# MainBoard_V1p0_SD.net
KiCad netlist of a schematic drawn in Altium Designer
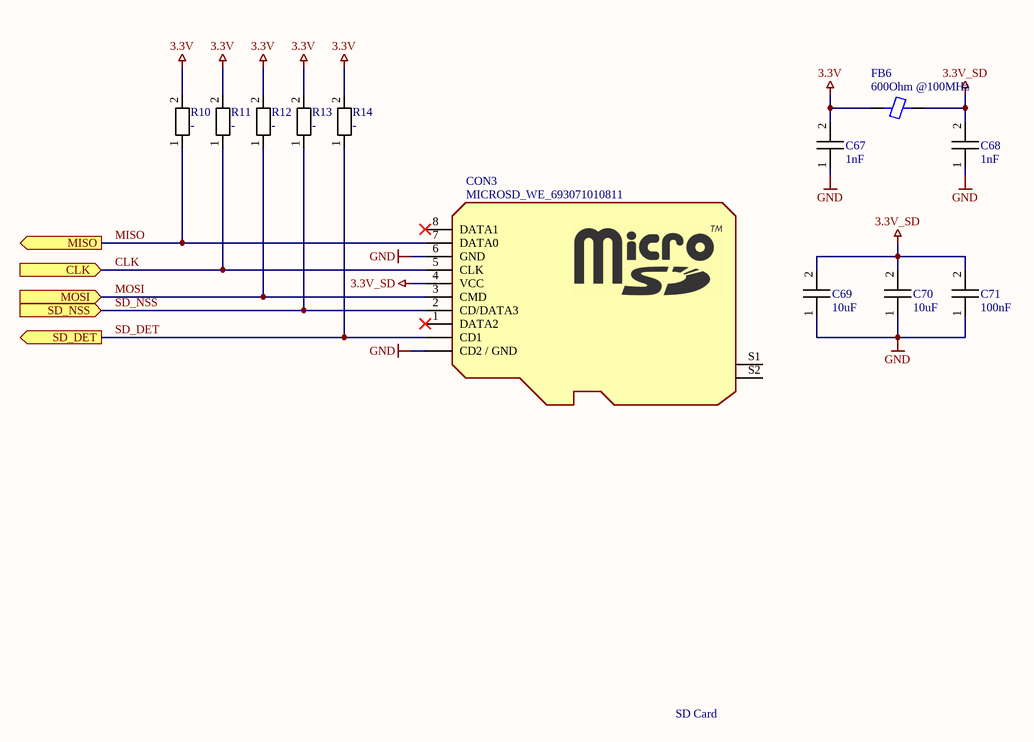
[diagram p0: MainBoard_V1p0_SD.SchDoc]

(export (version "E")
  (design (tool "Eeschema 10.0.6"))
  (components
    (comp (ref "C67") (value "1nF") (footprint "0805_C") (libsource (lib "Schlib1") (part "CAPACITOR")))
    (comp (ref "C68") (value "1nF") (footprint "0805_C") (libsource (lib "Schlib1") (part "CAPACITOR")))
    (comp (ref "C69") (value "10uF") (footprint "1210_C") (libsource (lib "Schlib1") (part "CAPACITOR")))
    (comp (ref "C70") (value "10uF") (footprint "1210_C") (libsource (lib "Schlib1") (part "CAPACITOR")))
    (comp (ref "C71") (value "100nF") (footprint "0805_C") (libsource (lib "Schlib1") (part "CAPACITOR")))
    (comp (ref "CON3")
      (value "MICROSD_WE_693071010811")
      (footprint "T_Wurth_693071010811")
      (libsource (lib "Schlib1") (part "MICROSD_WE_693071010811"))
    )
    (comp (ref "FB6")
      (value "600Ohm @100MHz")
      (footprint "0805_FB")
      (libsource (lib "Schlib1") (part "FERRITE_BEAD"))
    )
    (comp (ref "R10") (value "-") (footprint "0805") (libsource (lib "Schlib1") (part "RESISTOR")))
    (comp (ref "R11") (value "-") (footprint "0805") (libsource (lib "Schlib1") (part "RESISTOR")))
    (comp (ref "R12") (value "-") (footprint "0805") (libsource (lib "Schlib1") (part "RESISTOR")))
    (comp (ref "R13") (value "-") (footprint "0805") (libsource (lib "Schlib1") (part "RESISTOR")))
    (comp (ref "R14") (value "-") (footprint "0805") (libsource (lib "Schlib1") (part "RESISTOR")))
  )
  (nets
    (net (code "1") (name "/CLK") (class "Default")
      (node (ref "CON3") (pin "5") (pinfunction "CLK_5") (pintype "power_in"))
      (node (ref "R11") (pin "1") (pinfunction "0_1") (pintype "passive"))
    )
    (net (code "2") (name "/MISO") (class "Default")
      (node (ref "CON3") (pin "7") (pinfunction "DATA0_7") (pintype "power_in"))
      (node (ref "R10") (pin "1") (pinfunction "0_1") (pintype "passive"))
    )
    (net (code "3") (name "/MOSI") (class "Default")
      (node (ref "CON3") (pin "3") (pinfunction "CMD_3") (pintype "passive"))
      (node (ref "R12") (pin "1") (pinfunction "0_1") (pintype "passive"))
    )
    (net (code "4") (name "/SD_DET") (class "Default")
      (node (ref "CON3") (pin "CD1") (pinfunction "CD1_CD1") (pintype "power_in"))
      (node (ref "R14") (pin "1") (pinfunction "0_1") (pintype "passive"))
    )
    (net (code "5") (name "/SD_NSS") (class "Default")
      (node (ref "CON3") (pin "2") (pinfunction "CD/DATA3_2") (pintype "passive"))
      (node (ref "R13") (pin "1") (pinfunction "0_1") (pintype "passive"))
    )
    (net (code "6") (name "3.3V") (class "Default")
      (node (ref "C67") (pin "2") (pinfunction "2_2") (pintype "passive"))
      (node (ref "FB6") (pin "1") (pinfunction "1_1") (pintype "passive"))
      (node (ref "R10") (pin "2") (pinfunction "1_2") (pintype "passive"))
      (node (ref "R11") (pin "2") (pinfunction "1_2") (pintype "passive"))
      (node (ref "R12") (pin "2") (pinfunction "1_2") (pintype "passive"))
      (node (ref "R13") (pin "2") (pinfunction "1_2") (pintype "passive"))
      (node (ref "R14") (pin "2") (pinfunction "1_2") (pintype "passive"))
    )
    (net (code "7") (name "3.3V_SD") (class "Default")
      (node (ref "C68") (pin "2") (pinfunction "2_2") (pintype "passive"))
      (node (ref "C69") (pin "2") (pinfunction "2_2") (pintype "passive"))
      (node (ref "C70") (pin "2") (pinfunction "2_2") (pintype "passive"))
      (node (ref "C71") (pin "2") (pinfunction "2_2") (pintype "passive"))
      (node (ref "CON3") (pin "4") (pinfunction "VCC_4") (pintype "passive"))
      (node (ref "FB6") (pin "2") (pinfunction "2_2") (pintype "passive"))
    )
    (net (code "8") (name "GND") (class "Default")
      (node (ref "C67") (pin "1") (pinfunction "1_1") (pintype "passive"))
      (node (ref "C68") (pin "1") (pinfunction "1_1") (pintype "passive"))
      (node (ref "C69") (pin "1") (pinfunction "1_1") (pintype "passive"))
      (node (ref "C70") (pin "1") (pinfunction "1_1") (pintype "passive"))
      (node (ref "C71") (pin "1") (pinfunction "1_1") (pintype "passive"))
      (node (ref "CON3") (pin "6") (pinfunction "GND_6") (pintype "power_in"))
      (node (ref "CON3") (pin "CD2") (pinfunction "CD2_/_GND_CD2") (pintype "power_in"))
    )
    (net (code "9") (name "unconnected-(CON3-DATA1-Pad8)") (class "Default")
      (node (ref "CON3") (pin "8") (pinfunction "DATA1_8") (pintype "power_in+no_connect"))
    )
    (net (code "10") (name "unconnected-(CON3-DATA2-Pad1)") (class "Default")
      (node (ref "CON3") (pin "1") (pinfunction "DATA2_1") (pintype "power_in+no_connect"))
    )
    (net (code "11") (name "unconnected-(CON3-S-PadS1)") (class "Default")
      (node (ref "CON3") (pin "S1") (pinfunction "S_S1") (pintype "passive"))
    )
    (net (code "12") (name "unconnected-(CON3-S-PadS2)") (class "Default")
      (node (ref "CON3") (pin "S2") (pinfunction "S_S2") (pintype "passive"))
    )
  )
)
